# 06_MODEM.net
KiCad netlist of a schematic drawn in Altium Designer
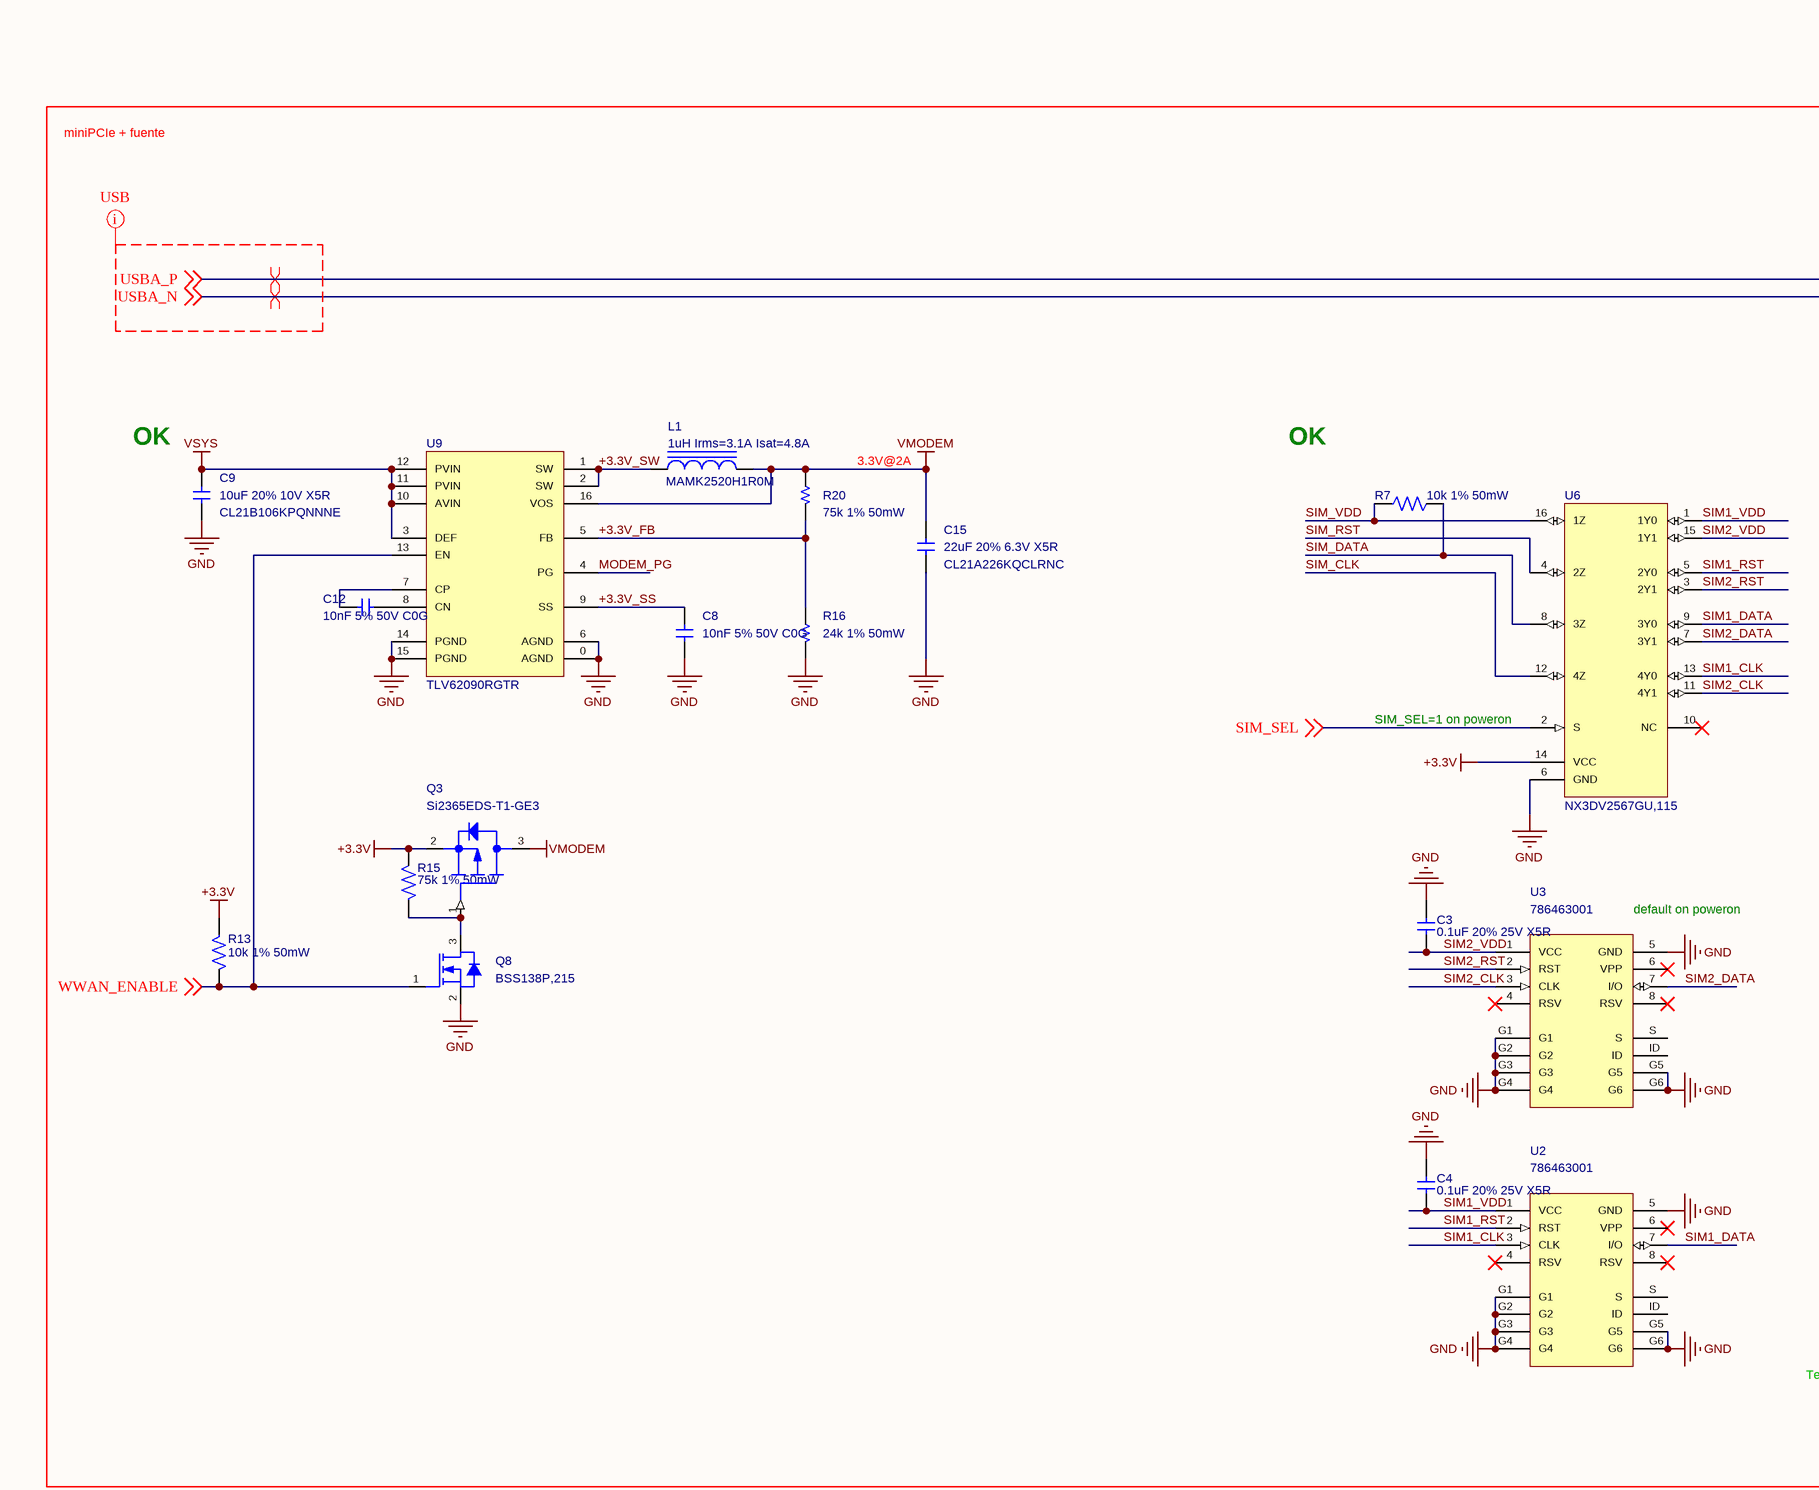
[diagram p0: 06_MODEM.SchDoc, left]
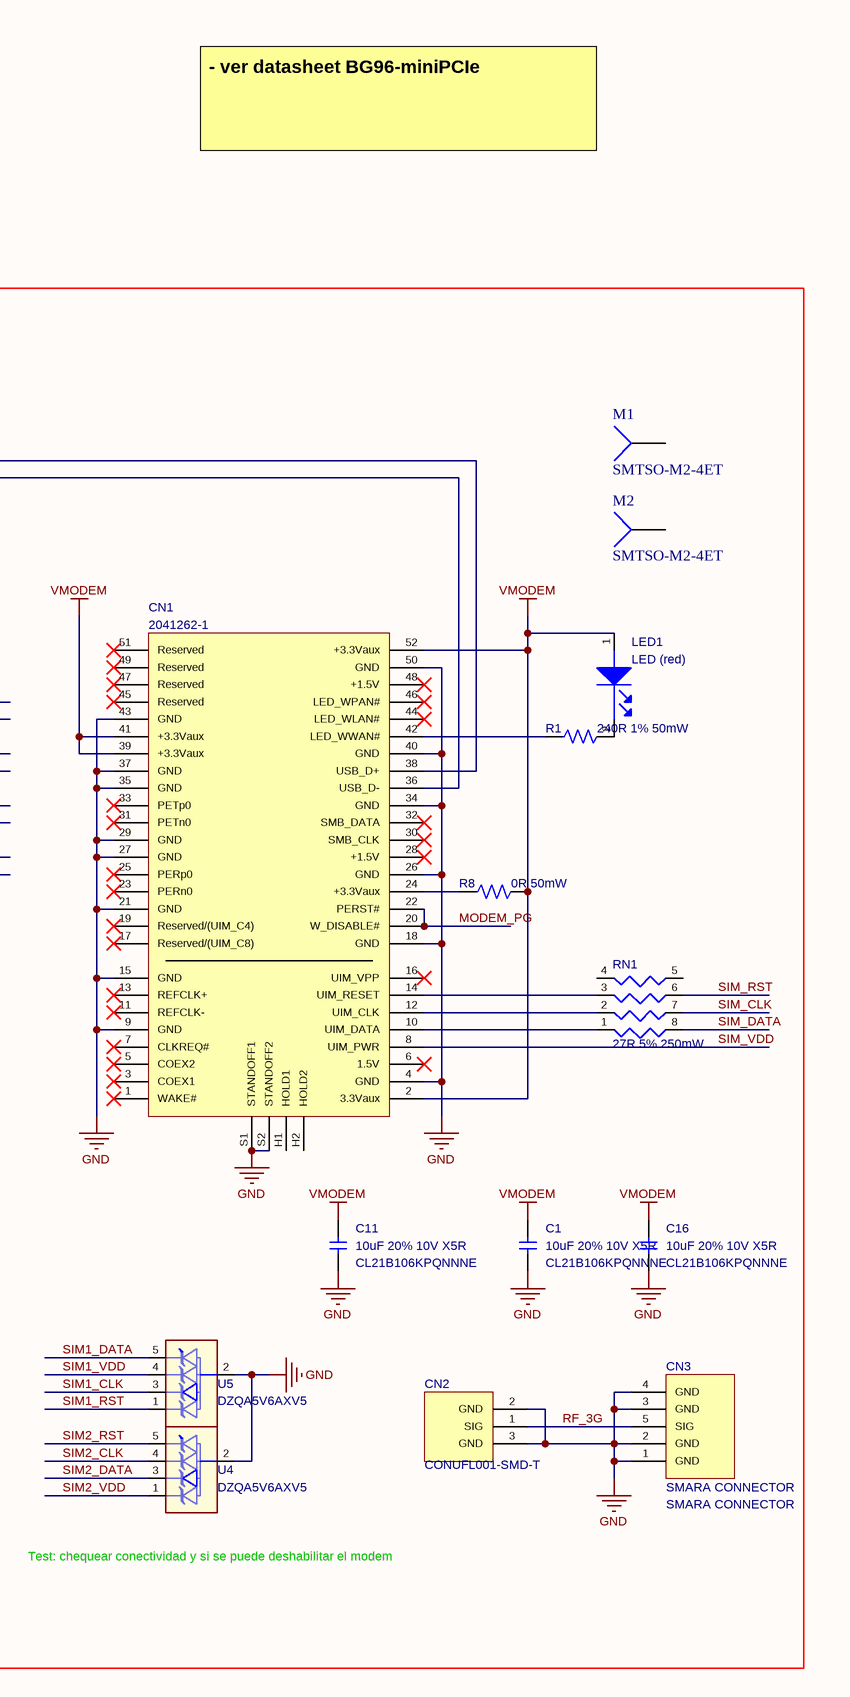
[diagram p1: 06_MODEM.SchDoc, right]

(export (version "E")
  (design (tool "Eeschema 10.0.6"))
  (components
    (comp (ref "C1")
      (value "10uF 20% 10V X5R")
      (footprint "CAPC2012X140N")
      (description "Capacitor, Ceramic")
      (fields
        (field (name "MFG") "SAMSUNG")
        (field (name "MFG_PN") "CL21B106KPQNNNE")
        (field (name "TOLERANCE") "20%")
        (field (name "FOOTPRINT CHECKED") "Assign OK, Footprint OK")
      )
      (libsource (lib "*") (part "C_Dup1"))
    )
    (comp (ref "C3")
      (value "0.1uF 20% 25V X5R")
      (footprint "CAPC1005N")
      (description "Capacitor, Ceramic")
      (fields
        (field (name "MFG") "SAMSUNG")
        (field (name "TOLERANCE") "20%")
        (field (name "FOOTPRINT CHECKED") "Assign OK, Footprint OK")
      )
      (libsource (lib "*") (part "C_Dup1"))
    )
    (comp (ref "C4")
      (value "0.1uF 20% 25V X5R")
      (footprint "CAPC1005N")
      (description "Capacitor, Ceramic")
      (fields
        (field (name "MFG") "SAMSUNG")
        (field (name "TOLERANCE") "20%")
        (field (name "FOOTPRINT CHECKED") "Assign OK, Footprint OK")
      )
      (libsource (lib "*") (part "C_Dup1"))
    )
    (comp (ref "C8")
      (value "10nF 5% 50V C0G")
      (footprint "CAPC1005N")
      (description "Capacitor, Ceramic")
      (fields
        (field (name "MFG") "<GENERIC>")
        (field (name "TOLERANCE") "5%")
        (field (name "FOOTPRINT CHECKED") "Assign OK, Footprint OK")
      )
      (libsource (lib "components") (part "C"))
    )
    (comp (ref "C9")
      (value "10uF 20% 10V X5R")
      (footprint "CAPC2012X140N")
      (description "Capacitor, Ceramic")
      (fields
        (field (name "MFG") "SAMSUNG")
        (field (name "MFG_PN") "CL21B106KPQNNNE")
        (field (name "TOLERANCE") "20%")
        (field (name "FOOTPRINT CHECKED") "Assign OK, Footprint OK")
      )
      (libsource (lib "*") (part "C_Dup1"))
    )
    (comp (ref "C11")
      (value "10uF 20% 10V X5R")
      (footprint "CAPC2012X140N")
      (description "Capacitor, Ceramic")
      (fields
        (field (name "MFG") "SAMSUNG")
        (field (name "MFG_PN") "CL21B106KPQNNNE")
        (field (name "TOLERANCE") "20%")
        (field (name "FOOTPRINT CHECKED") "Assign OK, Footprint OK")
      )
      (libsource (lib "*") (part "C_Dup1"))
    )
    (comp (ref "C12")
      (value "10nF 5% 50V C0G")
      (footprint "CAPC1005N")
      (description "Capacitor, Ceramic")
      (fields
        (field (name "MFG") "<GENERIC>")
        (field (name "TOLERANCE") "5%")
        (field (name "FOOTPRINT CHECKED") "Assign OK, Footprint OK")
      )
      (libsource (lib "components") (part "C"))
    )
    (comp (ref "C15")
      (value "22uF 20% 6.3V X5R")
      (footprint "CAPC2012X140N")
      (description "Capacitor, Ceramic")
      (fields
        (field (name "MFG") "SAMSUNG")
        (field (name "MFG_PN") "CL21A226KQCLRNC")
        (field (name "TOLERANCE") "20%")
        (field (name "FOOTPRINT CHECKED") "Assign OK, Footprint OK")
      )
      (libsource (lib "*") (part "C_Dup1"))
    )
    (comp (ref "C16")
      (value "10uF 20% 10V X5R")
      (footprint "CAPC2012X140N")
      (description "Capacitor, Ceramic")
      (fields
        (field (name "MFG") "SAMSUNG")
        (field (name "MFG_PN") "CL21B106KPQNNNE")
        (field (name "TOLERANCE") "20%")
        (field (name "FOOTPRINT CHECKED") "Assign OK, Footprint OK")
      )
      (libsource (lib "*") (part "C_Dup1"))
    )
    (comp (ref "CN1")
      (value "2041262-1")
      (footprint "2041262-1")
      (description "PCI Express Minicard Connector")
      (fields (field (name "MFG") "TE") (field (name "FOOTPRINT CHECKED") "Assign OK, Footprint OK"))
      (libsource (lib "traz") (part "miniPCIe"))
    )
    (comp (ref "CN2")
      (value "CONUFL001-SMD-T")
      (footprint "U.FL-R-SMT-1")
      (description "Ultra Small Surface Mount Coaxial Connectors - 1.9mm or 2.4mm Mated Height")
      (fields (field (name "MFG") "LINX") (field (name "FOOTPRINT CHECKED") "Assign OK, Footprint OK"))
      (libsource (lib "traz") (part "U.FL-R-SMT-1"))
    )
    (comp (ref "CN3")
      (value "SMARA CONNECTOR")
      (footprint "0733910320")
      (description "SMA, Right angle")
      (fields
        (field (name "MFG") "LPRS")
        (field (name "MFG_PN") "SMARA CONNECTOR")
        (field (name "FOOTPRINT CHECKED") "Assign OK, Footprint OK")
      )
      (libsource (lib "xct") (part "RPSMA"))
    )
    (comp (ref "L1")
      (value "1uH Irms=3.1A Isat=4.8A")
      (footprint "INDC2520N")
      (description "Inductor, Ferrite core")
      (fields
        (field (name "MFG") "TAIYO YUDEN")
        (field (name "MFG_PN") "MAMK2520H1R0M")
        (field (name "FOOTPRINT CHECKED") "Assign OK, Footprint OK")
      )
      (libsource (lib "components") (part "L_CORE"))
    )
    (comp (ref "LED1")
      (value "LED (red)")
      (footprint "LEDC1608N")
      (description "LED")
      (fields (field (name "MFG") "<GENERIC>") (field (name "FOOTPRINT CHECKED") "Assign OK, Footprint OK"))
      (libsource (lib "*") (part "Led Red HSMC-C170"))
    )
    (comp (ref "M1")
      (value "SMTSO-M2-4ET")
      (description "SMT nut, M2, H=4mm")
      (fields (field (name "MFG") "PEM") (field (name "FOOTPRINT CHECKED") "Assign OK, Footprint OK"))
      (libsource (lib "Miscellaneous Connectors") (part "Socket"))
    )
    (comp (ref "M2")
      (value "SMTSO-M2-4ET")
      (description "SMT nut, M2, H=4mm")
      (fields (field (name "MFG") "PEM") (field (name "FOOTPRINT CHECKED") "Assign OK, Footprint OK"))
      (libsource (lib "Miscellaneous Connectors") (part "Socket"))
    )
    (comp (ref "Q3")
      (value "Si2365EDS-T1-GE3")
      (footprint "SOT95P230X110-3N")
      (description "MOSFET, P channel")
      (fields (field (name "MFG") "VISHAY") (field (name "FOOTPRINT CHECKED") "Assign OK, Footprint OK"))
      (libsource (lib "traz") (part "DMG1013UW"))
    )
    (comp (ref "Q8")
      (value "BSS138P,215")
      (footprint "SOT95P230X110-3N")
      (description "MOSFET, N channel")
      (fields (field (name "MFG") "NXP") (field (name "FOOTPRINT CHECKED") "Assign OK, Footprint OK"))
      (libsource (lib "MCHP-CDB") (part "Transistor MOS-N GSD"))
    )
    (comp (ref "R1")
      (value "240R 1% 50mW")
      (footprint "RESC1005X40N")
      (description "Resistor, SMD")
      (fields
        (field (name "MFG") "<GENERIC>")
        (field (name "POWER") "50mW")
        (field (name "FOOTPRINT CHECKED") "Assign OK, Footprint OK")
      )
      (libsource (lib "*") (part "R"))
    )
    (comp (ref "R7")
      (value "10k 1% 50mW")
      (footprint "RESC1005X40N")
      (description "Resistor, SMD")
      (fields
        (field (name "MFG") "<GENERIC>")
        (field (name "POWER") "50mW")
        (field (name "FOOTPRINT CHECKED") "Assign OK, Footprint OK")
      )
      (libsource (lib "*") (part "R"))
    )
    (comp (ref "R8")
      (value "0R 50mW")
      (footprint "RESC1005X40N")
      (description "Resistor, SMD")
      (fields
        (field (name "MFG") "<GENERIC>")
        (field (name "POWER") "50mW")
        (field (name "FOOTPRINT CHECKED") "Assign OK, Footprint OK")
      )
      (libsource (lib "*") (part "R"))
    )
    (comp (ref "R13")
      (value "10k 1% 50mW")
      (footprint "RESC1005X40N")
      (description "Resistor, SMD")
      (fields
        (field (name "MFG") "<GENERIC>")
        (field (name "POWER") "50mW")
        (field (name "FOOTPRINT CHECKED") "Assign OK, Footprint OK")
      )
      (libsource (lib "*") (part "R"))
    )
    (comp (ref "R15")
      (value "75k 1% 50mW")
      (footprint "RESC1005X40N")
      (description "Resistor, SMD")
      (fields
        (field (name "MFG") "<GENERIC>")
        (field (name "POWER") "50mW")
        (field (name "FOOTPRINT CHECKED") "Assign OK, Footprint OK")
      )
      (libsource (lib "*") (part "R"))
    )
    (comp (ref "R16")
      (value "24k 1% 50mW")
      (footprint "RESC1005X40N")
      (description "Resistor, SMD")
      (fields
        (field (name "MFG") "<GENERIC>")
        (field (name "POWER") "50mW")
        (field (name "FOOTPRINT CHECKED") "Assign OK, Footprint OK")
      )
      (libsource (lib "components") (part "R"))
    )
    (comp (ref "R20")
      (value "75k 1% 50mW")
      (footprint "RESC1005X40N")
      (description "Resistor, SMD")
      (fields
        (field (name "MFG") "<GENERIC>")
        (field (name "POWER") "50mW")
        (field (name "FOOTPRINT CHECKED") "Assign OK, Footprint OK")
      )
      (libsource (lib "components") (part "R"))
    )
    (comp (ref "RN1")
      (value "27R 5% 250mW")
      (footprint "YC164")
      (description "Resistor array")
      (fields
        (field (name "MFG") "<GENERIC>")
        (field (name "POWER") "250mW")
        (field (name "FOOTPRINT CHECKED") "Assign OK, Footprint OK")
      )
      (libsource (lib "*") (part "RESNW_IS_0"))
    )
    (comp (ref "U2")
      (value "786463001")
      (footprint "786463001")
      (description "microSIM Card Holder")
      (fields (field (name "MFG") "MOLEX") (field (name "FOOTPRINT CHECKED") "Assign OK, Footprint OK"))
      (libsource (lib "traz") (part "115I-AEAA"))
    )
    (comp (ref "U3")
      (value "786463001")
      (footprint "786463001")
      (description "microSIM Card Holder")
      (fields (field (name "MFG") "MOLEX") (field (name "FOOTPRINT CHECKED") "Assign OK, Footprint OK"))
      (libsource (lib "traz") (part "115I-AEAA"))
    )
    (comp (ref "U4")
      (value "DZQA5V6AXV5")
      (footprint "SOTFL50P162X62-5N")
      (description "TVS array")
      (fields (field (name "MFG") "DIODES") (field (name "FOOTPRINT CHECKED") "Assign OK, Footprint OK"))
      (libsource (lib "traz") (part "PESD5V0L4UG"))
    )
    (comp (ref "U5")
      (value "DZQA5V6AXV5")
      (footprint "SOTFL50P162X62-5N")
      (description "TVS array")
      (fields (field (name "MFG") "DIODES") (field (name "FOOTPRINT CHECKED") "Assign OK, Footprint OK"))
      (libsource (lib "traz") (part "PESD5V0L4UG"))
    )
    (comp (ref "U6")
      (value "NX3DV2567GU,115")
      (footprint "XFQFN-16")
      (description "Low-ohmic four-pole double-throw analog switch")
      (fields (field (name "MFG") "NXP") (field (name "FOOTPRINT CHECKED") "Assign OK, Footprint OK"))
      (libsource (lib "sch") (part "NX3DV2567"))
    )
    (comp (ref "U9")
      (value "TLV62090RGTR")
      (footprint "QFN50P300X300X100-17AN-2")
      (description "Buck Switching Regulator IC Positive Adjustable 0.8V 1 Output 3A 16-VFQFN Exposed Pad")
      (fields (field (name "MFG") "TI") (field (name "FOOTPRINT CHECKED") "Assign OK, Footprint OK"))
      (libsource (lib "sch") (part "TLV62090RGTR"))
    )
  )
  (nets
    (net (code "1") (name "+3.3V") (class "Default")
      (node (ref "Q3") (pin "2") (pinfunction "SOURCE_2") (pintype "passive"))
      (node (ref "R13") (pin "1") (pinfunction "1_1") (pintype "passive"))
      (node (ref "R15") (pin "2") (pinfunction "2_2") (pintype "passive"))
      (node (ref "U6") (pin "14") (pinfunction "VCC_14") (pintype "power_in"))
    )
    (net (code "2") (name "/+3.3V_FB") (class "Default")
      (node (ref "R16") (pin "1") (pinfunction "1_1") (pintype "passive"))
      (node (ref "R20") (pin "2") (pinfunction "2_2") (pintype "passive"))
      (node (ref "U9") (pin "5") (pinfunction "FB_5") (pintype "passive"))
    )
    (net (code "3") (name "/+3.3V_SS") (class "Default")
      (node (ref "C8") (pin "2") (pinfunction "2_2") (pintype "passive"))
      (node (ref "U9") (pin "9") (pinfunction "SS_9") (pintype "passive"))
    )
    (net (code "4") (name "/+3.3V_SW") (class "Default")
      (node (ref "L1") (pin "1") (pinfunction "1_1") (pintype "passive"))
      (node (ref "U9") (pin "1") (pinfunction "SW_1") (pintype "passive"))
      (node (ref "U9") (pin "2") (pinfunction "SW_2") (pintype "passive"))
    )
    (net (code "5") (name "/MODEM_PG") (class "Default")
      (node (ref "CN1") (pin "20") (pinfunction "W_DISABLE#_20") (pintype "passive"))
      (node (ref "CN1") (pin "22") (pinfunction "PERST#_22") (pintype "passive"))
      (node (ref "U9") (pin "4") (pinfunction "PG_4") (pintype "passive"))
    )
    (net (code "6") (name "/RF_3G") (class "Default")
      (node (ref "CN2") (pin "1") (pinfunction "SIG_1") (pintype "passive"))
      (node (ref "CN3") (pin "5") (pinfunction "SIG_5") (pintype "passive"))
    )
    (net (code "7") (name "/SIM1_CLK") (class "Default")
      (node (ref "U2") (pin "3") (pinfunction "CLK_3") (pintype "input"))
      (node (ref "U5") (pin "3") (pinfunction "3_3") (pintype "passive"))
      (node (ref "U6") (pin "13") (pinfunction "4Y0_13") (pintype "bidirectional"))
    )
    (net (code "8") (name "/SIM1_DATA") (class "Default")
      (node (ref "U2") (pin "7") (pinfunction "I/O_7") (pintype "bidirectional"))
      (node (ref "U5") (pin "5") (pinfunction "5_5") (pintype "passive"))
      (node (ref "U6") (pin "9") (pinfunction "3Y0_9") (pintype "bidirectional"))
    )
    (net (code "9") (name "/SIM1_RST") (class "Default")
      (node (ref "U2") (pin "2") (pinfunction "RST_2") (pintype "input"))
      (node (ref "U5") (pin "1") (pinfunction "1_1") (pintype "passive"))
      (node (ref "U6") (pin "5") (pinfunction "2Y0_5") (pintype "bidirectional"))
    )
    (net (code "10") (name "/SIM1_VDD") (class "Default")
      (node (ref "C4") (pin "1") (pinfunction "1_1") (pintype "passive"))
      (node (ref "U2") (pin "1") (pinfunction "VCC_1") (pintype "power_in"))
      (node (ref "U5") (pin "4") (pinfunction "4_4") (pintype "passive"))
      (node (ref "U6") (pin "1") (pinfunction "1Y0_1") (pintype "bidirectional"))
    )
    (net (code "11") (name "/SIM2_CLK") (class "Default")
      (node (ref "U3") (pin "3") (pinfunction "CLK_3") (pintype "input"))
      (node (ref "U4") (pin "4") (pinfunction "4_4") (pintype "passive"))
      (node (ref "U6") (pin "11") (pinfunction "4Y1_11") (pintype "bidirectional"))
    )
    (net (code "12") (name "/SIM2_DATA") (class "Default")
      (node (ref "U3") (pin "7") (pinfunction "I/O_7") (pintype "bidirectional"))
      (node (ref "U4") (pin "3") (pinfunction "3_3") (pintype "passive"))
      (node (ref "U6") (pin "7") (pinfunction "3Y1_7") (pintype "bidirectional"))
    )
    (net (code "13") (name "/SIM2_RST") (class "Default")
      (node (ref "U3") (pin "2") (pinfunction "RST_2") (pintype "input"))
      (node (ref "U4") (pin "5") (pinfunction "5_5") (pintype "passive"))
      (node (ref "U6") (pin "3") (pinfunction "2Y1_3") (pintype "bidirectional"))
    )
    (net (code "14") (name "/SIM2_VDD") (class "Default")
      (node (ref "C3") (pin "1") (pinfunction "1_1") (pintype "passive"))
      (node (ref "U3") (pin "1") (pinfunction "VCC_1") (pintype "power_in"))
      (node (ref "U4") (pin "1") (pinfunction "1_1") (pintype "passive"))
      (node (ref "U6") (pin "15") (pinfunction "1Y1_15") (pintype "bidirectional"))
    )
    (net (code "15") (name "/SIM_CLK") (class "Default")
      (node (ref "RN1") (pin "7") (pinfunction "7_7") (pintype "passive"))
      (node (ref "U6") (pin "12") (pinfunction "4Z_12") (pintype "bidirectional"))
    )
    (net (code "16") (name "/SIM_DATA") (class "Default")
      (node (ref "R7") (pin "2") (pinfunction "2_2") (pintype "passive"))
      (node (ref "RN1") (pin "8") (pinfunction "8_8") (pintype "passive"))
      (node (ref "U6") (pin "8") (pinfunction "3Z_8") (pintype "bidirectional"))
    )
    (net (code "17") (name "/SIM_RST") (class "Default")
      (node (ref "RN1") (pin "6") (pinfunction "6_6") (pintype "passive"))
      (node (ref "U6") (pin "4") (pinfunction "2Z_4") (pintype "bidirectional"))
    )
    (net (code "18") (name "/SIM_VDD") (class "Default")
      (node (ref "CN1") (pin "8") (pinfunction "UIM_PWR_8") (pintype "passive"))
      (node (ref "R7") (pin "1") (pinfunction "1_1") (pintype "passive"))
      (node (ref "U6") (pin "16") (pinfunction "1Z_16") (pintype "bidirectional"))
    )
    (net (code "19") (name "GND") (class "Default")
      (node (ref "C1") (pin "2") (pinfunction "2_2") (pintype "passive"))
      (node (ref "C11") (pin "2") (pinfunction "2_2") (pintype "passive"))
      (node (ref "C15") (pin "2") (pinfunction "2_2") (pintype "passive"))
      (node (ref "C16") (pin "2") (pinfunction "2_2") (pintype "passive"))
      (node (ref "C3") (pin "2") (pinfunction "2_2") (pintype "passive"))
      (node (ref "C4") (pin "2") (pinfunction "2_2") (pintype "passive"))
      (node (ref "C8") (pin "1") (pinfunction "1_1") (pintype "passive"))
      (node (ref "C9") (pin "2") (pinfunction "2_2") (pintype "passive"))
      (node (ref "CN1") (pin "15") (pinfunction "GND_15") (pintype "passive"))
      (node (ref "CN1") (pin "18") (pinfunction "GND_18") (pintype "passive"))
      (node (ref "CN1") (pin "21") (pinfunction "GND_21") (pintype "passive"))
      (node (ref "CN1") (pin "26") (pinfunction "GND_26") (pintype "passive"))
      (node (ref "CN1") (pin "27") (pinfunction "GND_27") (pintype "passive"))
      (node (ref "CN1") (pin "29") (pinfunction "GND_29") (pintype "passive"))
      (node (ref "CN1") (pin "34") (pinfunction "GND_34") (pintype "passive"))
      (node (ref "CN1") (pin "35") (pinfunction "GND_35") (pintype "passive"))
      (node (ref "CN1") (pin "37") (pinfunction "GND_37") (pintype "passive"))
      (node (ref "CN1") (pin "4") (pinfunction "GND_4") (pintype "passive"))
      (node (ref "CN1") (pin "40") (pinfunction "GND_40") (pintype "passive"))
      (node (ref "CN1") (pin "43") (pinfunction "GND_43") (pintype "passive"))
      (node (ref "CN1") (pin "50") (pinfunction "GND_50") (pintype "passive"))
      (node (ref "CN1") (pin "9") (pinfunction "GND_9") (pintype "passive"))
      (node (ref "CN1") (pin "S1") (pinfunction "STANDOFF1_S1") (pintype "passive"))
      (node (ref "CN1") (pin "S2") (pinfunction "STANDOFF2_S2") (pintype "passive"))
      (node (ref "CN2") (pin "2") (pinfunction "GND_2") (pintype "passive"))
      (node (ref "CN2") (pin "3") (pinfunction "GND_3") (pintype "passive"))
      (node (ref "CN3") (pin "1") (pinfunction "GND_1") (pintype "passive"))
      (node (ref "CN3") (pin "2") (pinfunction "GND_2") (pintype "passive"))
      (node (ref "CN3") (pin "3") (pinfunction "GND_3") (pintype "passive"))
      (node (ref "CN3") (pin "4") (pinfunction "GND_4") (pintype "passive"))
      (node (ref "Q8") (pin "2") (pinfunction "S_2") (pintype "passive"))
      (node (ref "R16") (pin "2") (pinfunction "2_2") (pintype "passive"))
      (node (ref "U2") (pin "5") (pinfunction "GND_5") (pintype "power_in"))
      (node (ref "U2") (pin "G1") (pinfunction "G1_G1") (pintype "passive"))
      (node (ref "U2") (pin "G2") (pinfunction "G2_G2") (pintype "passive"))
      (node (ref "U2") (pin "G3") (pinfunction "G3_G3") (pintype "passive"))
      (node (ref "U2") (pin "G4") (pinfunction "G4_G4") (pintype "passive"))
      (node (ref "U2") (pin "G5") (pinfunction "G5_G5") (pintype "passive"))
      (node (ref "U2") (pin "G6") (pinfunction "G6_G6") (pintype "passive"))
      (node (ref "U3") (pin "5") (pinfunction "GND_5") (pintype "power_in"))
      (node (ref "U3") (pin "G1") (pinfunction "G1_G1") (pintype "passive"))
      (node (ref "U3") (pin "G2") (pinfunction "G2_G2") (pintype "passive"))
      (node (ref "U3") (pin "G3") (pinfunction "G3_G3") (pintype "passive"))
      (node (ref "U3") (pin "G4") (pinfunction "G4_G4") (pintype "passive"))
      (node (ref "U3") (pin "G5") (pinfunction "G5_G5") (pintype "passive"))
      (node (ref "U3") (pin "G6") (pinfunction "G6_G6") (pintype "passive"))
      (node (ref "U4") (pin "2") (pinfunction "2_2") (pintype "passive"))
      (node (ref "U5") (pin "2") (pinfunction "2_2") (pintype "passive"))
      (node (ref "U6") (pin "6") (pinfunction "GND_6") (pintype "power_in"))
      (node (ref "U9") (pin "0") (pinfunction "AGND_0") (pintype "passive"))
      (node (ref "U9") (pin "14") (pinfunction "PGND_14") (pintype "passive"))
      (node (ref "U9") (pin "15") (pinfunction "PGND_15") (pintype "passive"))
      (node (ref "U9") (pin "6") (pinfunction "AGND_6") (pintype "passive"))
    )
    (net (code "20") (name "Net-(CN1-+3.3Vaux-Pad24)") (class "Default")
      (node (ref "CN1") (pin "24") (pinfunction "+3.3Vaux_24") (pintype "passive"))
      (node (ref "R8") (pin "1") (pinfunction "1_1") (pintype "passive"))
    )
    (net (code "21") (name "Net-(CN1-LED_WWAN#)") (class "Default")
      (node (ref "CN1") (pin "42") (pinfunction "LED_WWAN#_42") (pintype "passive"))
      (node (ref "R1") (pin "1") (pinfunction "1_1") (pintype "passive"))
    )
    (net (code "22") (name "Net-(CN1-UIM_CLK)") (class "Default")
      (node (ref "CN1") (pin "12") (pinfunction "UIM_CLK_12") (pintype "passive"))
      (node (ref "RN1") (pin "2") (pinfunction "2_2") (pintype "passive"))
    )
    (net (code "23") (name "Net-(CN1-UIM_DATA)") (class "Default")
      (node (ref "CN1") (pin "10") (pinfunction "UIM_DATA_10") (pintype "passive"))
      (node (ref "RN1") (pin "1") (pinfunction "1_1") (pintype "passive"))
    )
    (net (code "24") (name "Net-(CN1-UIM_RESET)") (class "Default")
      (node (ref "CN1") (pin "14") (pinfunction "UIM_RESET_14") (pintype "passive"))
      (node (ref "RN1") (pin "3") (pinfunction "3_3") (pintype "passive"))
    )
    (net (code "25") (name "Net-(LED1-ANODE)") (class "Default")
      (node (ref "LED1") (pin "2") (pinfunction "ANODE_2") (pintype "passive"))
      (node (ref "R1") (pin "2") (pinfunction "2_2") (pintype "passive"))
    )
    (net (code "26") (name "Net-(Q3-GATE)") (class "Default")
      (node (ref "Q3") (pin "1") (pinfunction "GATE_1") (pintype "input"))
      (node (ref "Q8") (pin "3") (pinfunction "D_3") (pintype "passive"))
      (node (ref "R15") (pin "1") (pinfunction "1_1") (pintype "passive"))
    )
    (net (code "27") (name "Net-(U9-CN)") (class "Default")
      (node (ref "C12") (pin "2") (pinfunction "2_2") (pintype "passive"))
      (node (ref "U9") (pin "8") (pinfunction "CN_8") (pintype "passive"))
    )
    (net (code "28") (name "Net-(U9-CP)") (class "Default")
      (node (ref "C12") (pin "1") (pinfunction "1_1") (pintype "passive"))
      (node (ref "U9") (pin "7") (pinfunction "CP_7") (pintype "passive"))
    )
    (net (code "29") (name "SIM_SEL") (class "Default")
      (node (ref "U6") (pin "2") (pinfunction "S_2") (pintype "input"))
    )
    (net (code "30") (name "USBA_N") (class "Default")
      (node (ref "CN1") (pin "36") (pinfunction "USB_D-_36") (pintype "passive"))
    )
    (net (code "31") (name "USBA_P") (class "Default")
      (node (ref "CN1") (pin "38") (pinfunction "USB_D+_38") (pintype "passive"))
    )
    (net (code "32") (name "VMODEM") (class "Default")
      (node (ref "C1") (pin "1") (pinfunction "1_1") (pintype "passive"))
      (node (ref "C11") (pin "1") (pinfunction "1_1") (pintype "passive"))
      (node (ref "C15") (pin "1") (pinfunction "1_1") (pintype "passive"))
      (node (ref "C16") (pin "1") (pinfunction "1_1") (pintype "passive"))
      (node (ref "CN1") (pin "2") (pinfunction "3.3Vaux_2") (pintype "passive"))
      (node (ref "CN1") (pin "39") (pinfunction "+3.3Vaux_39") (pintype "passive"))
      (node (ref "CN1") (pin "41") (pinfunction "+3.3Vaux_41") (pintype "passive"))
      (node (ref "CN1") (pin "52") (pinfunction "+3.3Vaux_52") (pintype "passive"))
      (node (ref "L1") (pin "2") (pinfunction "2_2") (pintype "passive"))
      (node (ref "LED1") (pin "1") (pinfunction "CATHODE_1") (pintype "passive"))
      (node (ref "Q3") (pin "3") (pinfunction "DRAIN_3") (pintype "passive"))
      (node (ref "R20") (pin "1") (pinfunction "1_1") (pintype "passive"))
      (node (ref "R8") (pin "2") (pinfunction "2_2") (pintype "passive"))
      (node (ref "U9") (pin "16") (pinfunction "VOS_16") (pintype "passive"))
    )
    (net (code "33") (name "VSYS") (class "Default")
      (node (ref "C9") (pin "1") (pinfunction "1_1") (pintype "passive"))
      (node (ref "U9") (pin "10") (pinfunction "AVIN_10") (pintype "passive"))
      (node (ref "U9") (pin "11") (pinfunction "PVIN_11") (pintype "passive"))
      (node (ref "U9") (pin "12") (pinfunction "PVIN_12") (pintype "passive"))
      (node (ref "U9") (pin "3") (pinfunction "DEF_3") (pintype "passive"))
    )
    (net (code "34") (name "WWAN_ENABLE") (class "Default")
      (node (ref "Q8") (pin "1") (pinfunction "G_1") (pintype "passive"))
      (node (ref "R13") (pin "2") (pinfunction "2_2") (pintype "passive"))
      (node (ref "U9") (pin "13") (pinfunction "EN_13") (pintype "passive"))
    )
    (net (code "35") (name "unconnected-(CN1-+1.5V-Pad28)") (class "Default")
      (node (ref "CN1") (pin "28") (pinfunction "+1.5V_28") (pintype "passive+no_connect"))
    )
    (net (code "36") (name "unconnected-(CN1-+1.5V-Pad48)") (class "Default")
      (node (ref "CN1") (pin "48") (pinfunction "+1.5V_48") (pintype "passive+no_connect"))
    )
    (net (code "37") (name "unconnected-(CN1-1.5V-Pad6)") (class "Default")
      (node (ref "CN1") (pin "6") (pinfunction "1.5V_6") (pintype "passive+no_connect"))
    )
    (net (code "38") (name "unconnected-(CN1-CLKREQ#-Pad7)") (class "Default")
      (node (ref "CN1") (pin "7") (pinfunction "CLKREQ#_7") (pintype "passive+no_connect"))
    )
    (net (code "39") (name "unconnected-(CN1-COEX1-Pad3)") (class "Default")
      (node (ref "CN1") (pin "3") (pinfunction "COEX1_3") (pintype "passive+no_connect"))
    )
    (net (code "40") (name "unconnected-(CN1-COEX2-Pad5)") (class "Default")
      (node (ref "CN1") (pin "5") (pinfunction "COEX2_5") (pintype "passive+no_connect"))
    )
    (net (code "41") (name "unconnected-(CN1-HOLD1-PadH1)") (class "Default")
      (node (ref "CN1") (pin "H1") (pinfunction "HOLD1_H1") (pintype "passive"))
    )
    (net (code "42") (name "unconnected-(CN1-HOLD2-PadH2)") (class "Default")
      (node (ref "CN1") (pin "H2") (pinfunction "HOLD2_H2") (pintype "passive"))
    )
    (net (code "43") (name "unconnected-(CN1-LED_WLAN#-Pad44)") (class "Default")
      (node (ref "CN1") (pin "44") (pinfunction "LED_WLAN#_44") (pintype "passive+no_connect"))
    )
    (net (code "44") (name "unconnected-(CN1-LED_WPAN#-Pad46)") (class "Default")
      (node (ref "CN1") (pin "46") (pinfunction "LED_WPAN#_46") (pintype "passive+no_connect"))
    )
    (net (code "45") (name "unconnected-(CN1-PERn0-Pad23)") (class "Default")
      (node (ref "CN1") (pin "23") (pinfunction "PERn0_23") (pintype "passive+no_connect"))
    )
    (net (code "46") (name "unconnected-(CN1-PERp0-Pad25)") (class "Default")
      (node (ref "CN1") (pin "25") (pinfunction "PERp0_25") (pintype "passive+no_connect"))
    )
    (net (code "47") (name "unconnected-(CN1-PETn0-Pad31)") (class "Default")
      (node (ref "CN1") (pin "31") (pinfunction "PETn0_31") (pintype "passive+no_connect"))
    )
    (net (code "48") (name "unconnected-(CN1-PETp0-Pad33)") (class "Default")
      (node (ref "CN1") (pin "33") (pinfunction "PETp0_33") (pintype "passive+no_connect"))
    )
    (net (code "49") (name "unconnected-(CN1-REFCLK+-Pad13)") (class "Default")
      (node (ref "CN1") (pin "13") (pinfunction "REFCLK+_13") (pintype "passive+no_connect"))
    )
    (net (code "50") (name "unconnected-(CN1-REFCLK--Pad11)") (class "Default")
      (node (ref "CN1") (pin "11") (pinfunction "REFCLK-_11") (pintype "passive+no_connect"))
    )
    (net (code "51") (name "unconnected-(CN1-Reserved-Pad45)") (class "Default")
      (node (ref "CN1") (pin "45") (pinfunction "Reserved_45") (pintype "passive+no_connect"))
    )
    (net (code "52") (name "unconnected-(CN1-Reserved-Pad47)") (class "Default")
      (node (ref "CN1") (pin "47") (pinfunction "Reserved_47") (pintype "passive+no_connect"))
    )
    (net (code "53") (name "unconnected-(CN1-Reserved-Pad49)") (class "Default")
      (node (ref "CN1") (pin "49") (pinfunction "Reserved_49") (pintype "passive+no_connect"))
    )
    (net (code "54") (name "unconnected-(CN1-Reserved-Pad51)") (class "Default")
      (node (ref "CN1") (pin "51") (pinfunction "Reserved_51") (pintype "passive+no_connect"))
    )
    (net (code "55") (name "unconnected-(CN1-Reserved{slash}(UIM_C4)-Pad19)") (class "Default")
      (node (ref "CN1") (pin "19") (pinfunction "Reserved/(UIM_C4)_19") (pintype "passive+no_connect"))
    )
    (net (code "56") (name "unconnected-(CN1-Reserved{slash}(UIM_C8)-Pad17)") (class "Default")
      (node (ref "CN1") (pin "17") (pinfunction "Reserved/(UIM_C8)_17") (pintype "passive+no_connect"))
    )
    (net (code "57") (name "unconnected-(CN1-SMB_CLK-Pad30)") (class "Default")
      (node (ref "CN1") (pin "30") (pinfunction "SMB_CLK_30") (pintype "passive+no_connect"))
    )
    (net (code "58") (name "unconnected-(CN1-SMB_DATA-Pad32)") (class "Default")
      (node (ref "CN1") (pin "32") (pinfunction "SMB_DATA_32") (pintype "passive+no_connect"))
    )
    (net (code "59") (name "unconnected-(CN1-UIM_VPP-Pad16)") (class "Default")
      (node (ref "CN1") (pin "16") (pinfunction "UIM_VPP_16") (pintype "passive+no_connect"))
    )
    (net (code "60") (name "unconnected-(CN1-WAKE#-Pad1)") (class "Default")
      (node (ref "CN1") (pin "1") (pinfunction "WAKE#_1") (pintype "passive+no_connect"))
    )
    (net (code "61") (name "unconnected-(M1-Pad1)") (class "Default")
      (node (ref "M1") (pin "1") (pinfunction "1_1") (pintype "passive"))
    )
    (net (code "62") (name "unconnected-(M2-Pad1)") (class "Default")
      (node (ref "M2") (pin "1") (pinfunction "1_1") (pintype "passive"))
    )
    (net (code "63") (name "unconnected-(RN1-Pad4)") (class "Default")
      (node (ref "RN1") (pin "4") (pinfunction "4_4") (pintype "passive"))
    )
    (net (code "64") (name "unconnected-(RN1-Pad5)") (class "Default")
      (node (ref "RN1") (pin "5") (pinfunction "5_5") (pintype "passive"))
    )
    (net (code "65") (name "unconnected-(U2-PadID)") (class "Default")
      (node (ref "U2") (pin "ID") (pinfunction "ID_ID") (pintype "passive"))
    )
    (net (code "66") (name "unconnected-(U2-PadS)") (class "Default")
      (node (ref "U2") (pin "S") (pinfunction "S_S") (pintype "passive"))
    )
    (net (code "67") (name "unconnected-(U2-RSV-Pad4)") (class "Default")
      (node (ref "U2") (pin "4") (pinfunction "RSV_4") (pintype "passive+no_connect"))
    )
    (net (code "68") (name "unconnected-(U2-RSV-Pad8)") (class "Default")
      (node (ref "U2") (pin "8") (pinfunction "RSV_8") (pintype "passive+no_connect"))
    )
    (net (code "69") (name "unconnected-(U2-VPP-Pad6)") (class "Default")
      (node (ref "U2") (pin "6") (pinfunction "VPP_6") (pintype "power_in+no_connect"))
    )
    (net (code "70") (name "unconnected-(U3-PadID)") (class "Default")
      (node (ref "U3") (pin "ID") (pinfunction "ID_ID") (pintype "passive"))
    )
    (net (code "71") (name "unconnected-(U3-PadS)") (class "Default")
      (node (ref "U3") (pin "S") (pinfunction "S_S") (pintype "passive"))
    )
    (net (code "72") (name "unconnected-(U3-RSV-Pad4)") (class "Default")
      (node (ref "U3") (pin "4") (pinfunction "RSV_4") (pintype "passive+no_connect"))
    )
    (net (code "73") (name "unconnected-(U3-RSV-Pad8)") (class "Default")
      (node (ref "U3") (pin "8") (pinfunction "RSV_8") (pintype "passive+no_connect"))
    )
    (net (code "74") (name "unconnected-(U3-VPP-Pad6)") (class "Default")
      (node (ref "U3") (pin "6") (pinfunction "VPP_6") (pintype "power_in+no_connect"))
    )
    (net (code "75") (name "unconnected-(U6-NC-Pad10)") (class "Default")
      (node (ref "U6") (pin "10") (pinfunction "NC_10") (pintype "passive+no_connect"))
    )
  )
)
